# DriverControlsCarrierboard.net
KiCad netlist of a schematic drawn in Altium Designer
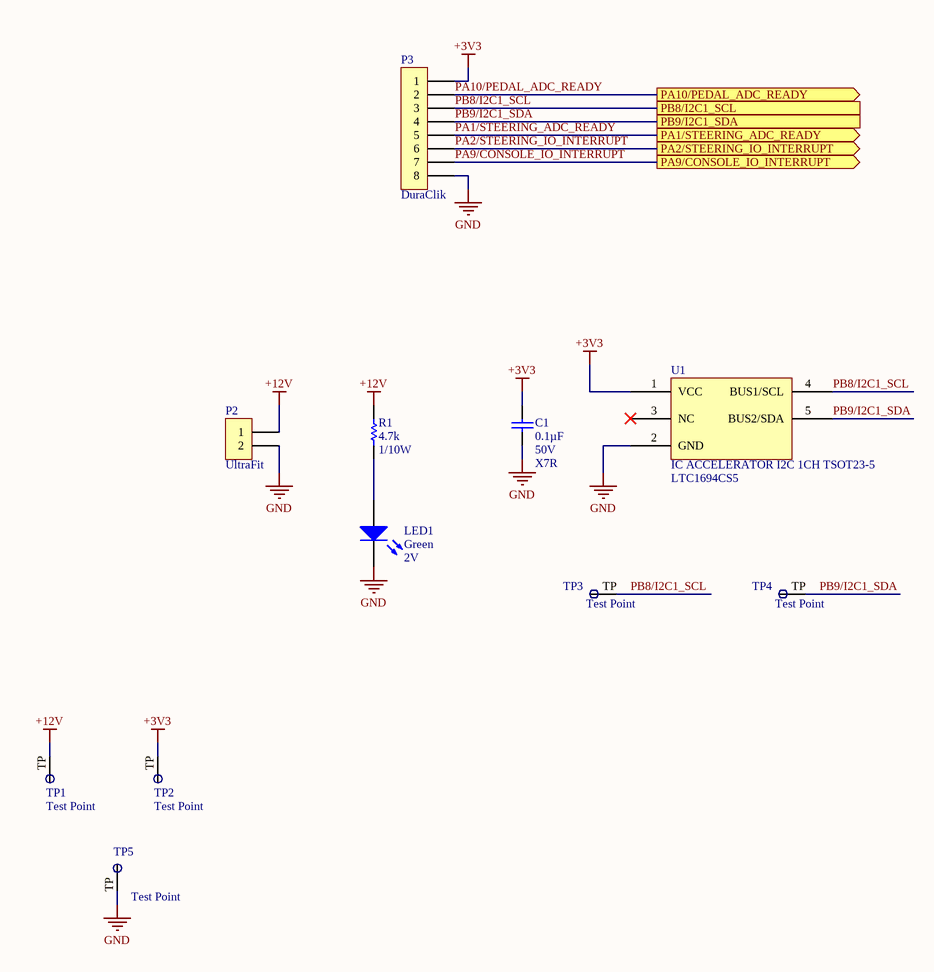
[diagram p0: DriverControlsCarrierboard.SchDoc]

(export (version "E")
  (design (tool "Eeschema 10.0.6"))
  (components
    (comp (ref "C1")
      (value "CAP CER 0.1UF 50V 10% X7R 0603")
      (footprint "CAP, 0603")
      (description "0.10µF ±10% 50V Ceramic Capacitor X7R 0603 (1608 Metric)")
      (fields
        (field (name "TOLERANCE") "±10%")
        (field (name "CAPACITANCE") "0.1µF")
        (field (name "VOLTAGE") "50V")
        (field (name "TEMPERATURE COEFFICIENT") "X7R")
      )
      (libsource (lib "Schematic Diagrams") (part "CAP CER 0.1UF 50V 10% X7R 0603"))
    )
    (comp (ref "LED1")
      (value "LED GREEN CLEAR 2V 0603")
      (footprint "LED_0603")
      (description "Green 572nm LED Indication - Discrete 2V 0603 (1608 Metric)")
      (fields
        (field (name "MANUFACTURER") "Wurth Electronics Inc.")
        (field (name "MANUFACTURER PART NUMBER") "150060VS75000")
        (field (name "COLOR") "Green")
        (field (name "VOLTAGE - FORWARD (VF) (TYP)") "2V")
      )
      (libsource (lib "Schematic Diagrams") (part "LED GREEN CLEAR 2V 0603"))
    )
    (comp (ref "P2")
      (value "CONN 2POS ULTRA-FIT 0.138\"")
      (footprint "CONN, 2POS ULTRA-FIT")
      (description "2 Positions Header, Shrouded Connector 0.138\" (3.50mm) Through Hole Gold")
      (fields (field (name "VOLTAGE") "400V") (field (name "SERIES") "UltraFit"))
      (libsource (lib "Schematic Diagrams") (part "CONN 2POS ULTRA-FIT 0.138{dblquote}"))
    )
    (comp (ref "P3")
      (value "CONN 8POS DURA-CLIK 0.079\"")
      (footprint "CONN, 8POS Dura-Clik")
      (description "8 Positions Header Connector 0.079\" (2.00mm) Surface Mount Tin")
      (fields (field (name "SERIES") "DuraClik"))
      (libsource (lib "Schematic Diagrams") (part "CONN 8POS DURA-CLIK 0.079{dblquote}"))
    )
    (comp (ref "R1")
      (value "RES 4.7K OHM 1% 1/10W 0603")
      (footprint "RES, 0603")
      (description "4.7k Ohm ±1% 0.1W, 1/10W Chip Resistor 0603 (1608 Metric) Moisture Resistant Thick Film")
      (fields
        (field (name "TOLERANCE") "±1%")
        (field (name "RESISTANCE (OHMS)") "4.7k")
        (field (name "POWER (WATTS)") "1/10W")
      )
      (libsource (lib "Schematic Diagrams") (part "RES 4.7K OHM 1% 1/10W 0603"))
    )
    (comp (ref "TP1")
      (value "Test Point")
      (footprint "Test Point")
      (libsource (lib "Schematic Diagrams") (part "Test Point"))
    )
    (comp (ref "TP2")
      (value "Test Point")
      (footprint "Test Point")
      (libsource (lib "Schematic Diagrams") (part "Test Point"))
    )
    (comp (ref "TP3")
      (value "Test Point")
      (footprint "Test Point")
      (libsource (lib "Schematic Diagrams") (part "Test Point"))
    )
    (comp (ref "TP4")
      (value "Test Point")
      (footprint "Test Point")
      (libsource (lib "Schematic Diagrams") (part "Test Point"))
    )
    (comp (ref "TP5")
      (value "Test Point")
      (footprint "Test Point")
      (libsource (lib "Schematic Diagrams") (part "Test Point"))
    )
    (comp (ref "U1")
      (value "IC ACCELERATOR I2C 1CH TSOT23-5")
      (footprint "IC OP AMP GP RR 10MHZ SOT-23-5")
      (description "Accelerator 1 Channel 400kHz TSOT-23-5")
      (fields
        (field (name "MANUFACTURER") "Linear Technology/Analog Devices")
        (field (name "MANUFACTURER PART NUMBER") "LTC1694CS5#TRMPBF")
        (field (name "SUPPLIER PART NUMBER") "LTC1694CS5")
      )
      (libsource (lib "Schematic Diagrams") (part "IC ACCELERATOR I2C 1CH TSOT23-5"))
    )
  )
  (nets
    (net (code "1") (name "+3V3") (class "Default")
      (node (ref "C1") (pin "1") (pinfunction "1_1") (pintype "passive"))
      (node (ref "P3") (pin "1") (pinfunction "1_1") (pintype "passive"))
      (node (ref "TP2") (pin "TP") (pinfunction "1_TP") (pintype "passive"))
      (node (ref "U1") (pin "1") (pinfunction "VCC_1") (pintype "passive"))
    )
    (net (code "2") (name "+12V") (class "Default")
      (node (ref "P2") (pin "1") (pinfunction "1_1") (pintype "passive"))
      (node (ref "R1") (pin "1") (pinfunction "1_1") (pintype "passive"))
      (node (ref "TP1") (pin "TP") (pinfunction "1_TP") (pintype "passive"))
    )
    (net (code "3") (name "/PA1{slash}STEERING_ADC_READY") (class "Default")
      (node (ref "P3") (pin "5") (pinfunction "5_5") (pintype "passive"))
    )
    (net (code "4") (name "/PA2{slash}STEERING_IO_INTERRUPT") (class "Default")
      (node (ref "P3") (pin "6") (pinfunction "6_6") (pintype "passive"))
    )
    (net (code "5") (name "/PA9{slash}CONSOLE_IO_INTERRUPT") (class "Default")
      (node (ref "P3") (pin "7") (pinfunction "7_7") (pintype "passive"))
    )
    (net (code "6") (name "/PA10{slash}PEDAL_ADC_READY") (class "Default")
      (node (ref "P3") (pin "2") (pinfunction "2_2") (pintype "passive"))
    )
    (net (code "7") (name "/PB8{slash}I2C1_SCL") (class "Default")
      (node (ref "P3") (pin "3") (pinfunction "3_3") (pintype "passive"))
      (node (ref "TP3") (pin "TP") (pinfunction "1_TP") (pintype "passive"))
      (node (ref "U1") (pin "4") (pinfunction "BUS1/SCL_4") (pintype "passive"))
    )
    (net (code "8") (name "/PB9{slash}I2C1_SDA") (class "Default")
      (node (ref "P3") (pin "4") (pinfunction "4_4") (pintype "passive"))
      (node (ref "TP4") (pin "TP") (pinfunction "1_TP") (pintype "passive"))
      (node (ref "U1") (pin "5") (pinfunction "BUS2/SDA_5") (pintype "passive"))
    )
    (net (code "9") (name "GND") (class "Default")
      (node (ref "C1") (pin "2") (pinfunction "2_2") (pintype "passive"))
      (node (ref "LED1") (pin "2") (pinfunction "K_2") (pintype "passive"))
      (node (ref "P2") (pin "2") (pinfunction "2_2") (pintype "passive"))
      (node (ref "P3") (pin "8") (pinfunction "8_8") (pintype "passive"))
      (node (ref "TP5") (pin "TP") (pinfunction "1_TP") (pintype "passive"))
      (node (ref "U1") (pin "2") (pinfunction "GND_2") (pintype "passive"))
    )
    (net (code "10") (name "Net-(LED1-A)") (class "Default")
      (node (ref "LED1") (pin "1") (pinfunction "A_1") (pintype "passive"))
      (node (ref "R1") (pin "2") (pinfunction "2_2") (pintype "passive"))
    )
    (net (code "11") (name "unconnected-(U1-NC-Pad3)") (class "Default")
      (node (ref "U1") (pin "3") (pinfunction "NC_3") (pintype "passive+no_connect"))
    )
  )
)
